# MainBoard.net
KiCad netlist of a schematic drawn in EAGLE
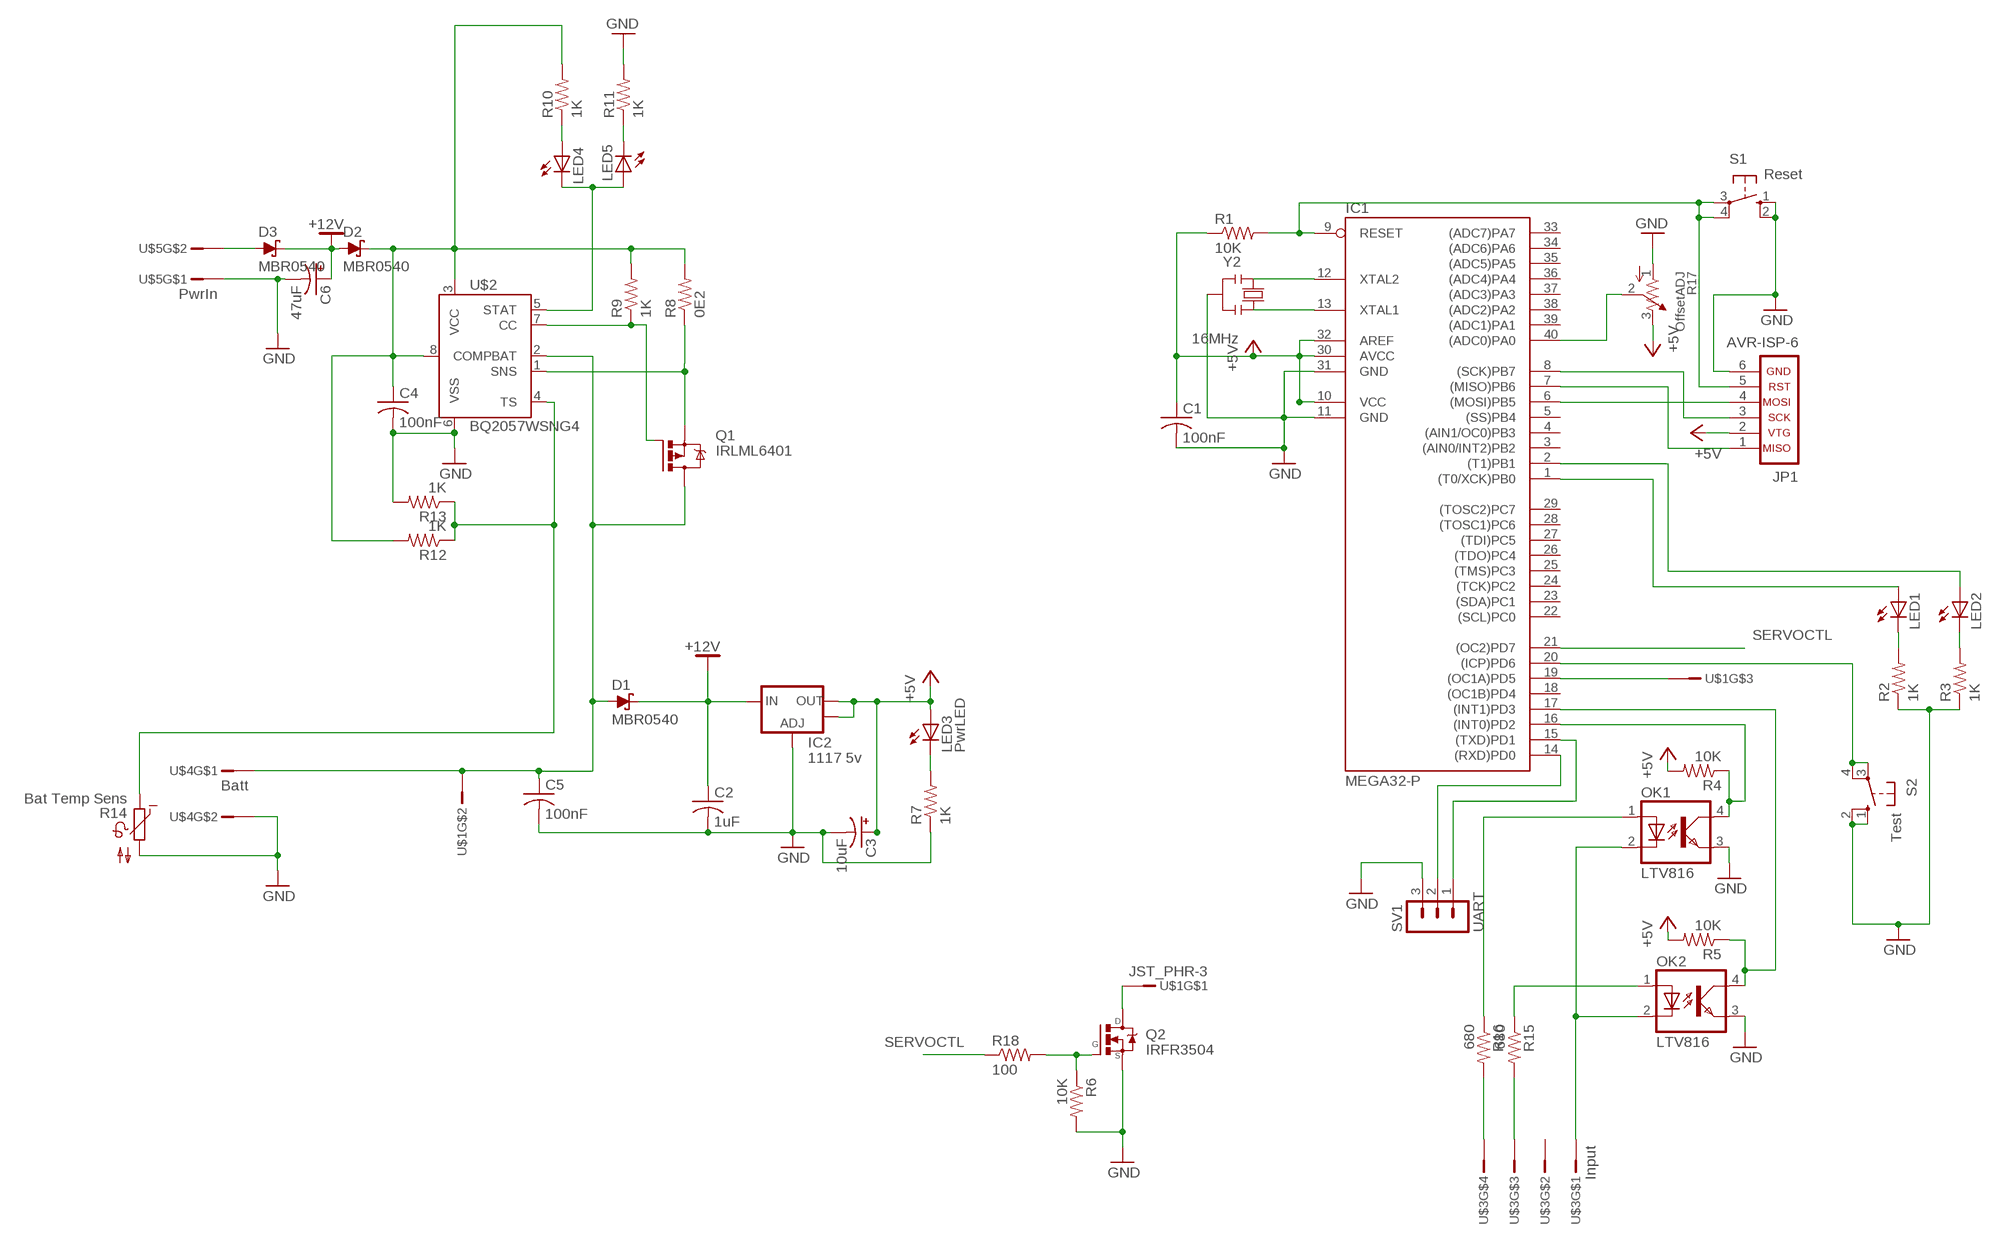
[diagram p0: schematic, sheet 1]

(export (version "E")
  (design (tool "Eeschema 10.0.6"))
  (components
    (comp (ref "C1")
      (value "100nF")
      (footprint "eagle-import:C0805K")
      (libsource (lib "eagle-import") (part "C-USC0805K"))
    )
    (comp (ref "C2")
      (value "1uF")
      (footprint "eagle-import:C0805K")
      (libsource (lib "eagle-import") (part "C-USC0805K"))
    )
    (comp (ref "C3")
      (value "10uF")
      (footprint "eagle-import:E2,5-7")
      (libsource (lib "eagle-import") (part "CPOL-USE2.5-7"))
    )
    (comp (ref "C4")
      (value "100nF")
      (footprint "eagle-import:C0805K")
      (libsource (lib "eagle-import") (part "C-USC0805K"))
    )
    (comp (ref "C5")
      (value "100nF")
      (footprint "eagle-import:C0805K")
      (libsource (lib "eagle-import") (part "C-USC0805K"))
    )
    (comp (ref "C6")
      (value "47uF")
      (footprint "eagle-import:E2,5-7")
      (libsource (lib "eagle-import") (part "CPOL-USE2.5-7"))
    )
    (comp (ref "D1")
      (value "MBR0540")
      (footprint "eagle-import:SOD123")
      (libsource (lib "eagle-import") (part "MBR0540"))
    )
    (comp (ref "D2")
      (value "MBR0540")
      (footprint "eagle-import:SOD123")
      (libsource (lib "eagle-import") (part "MBR0540"))
    )
    (comp (ref "D3")
      (value "MBR0540")
      (footprint "eagle-import:SOD123")
      (libsource (lib "eagle-import") (part "MBR0540"))
    )
    (comp (ref "IC1")
      (value "MEGA32-P")
      (footprint "eagle-import:DIL40")
      (fields (field (name "MPN") "ATMEGA32-16PU"))
      (libsource (lib "eagle-import") (part "MEGA32-P"))
    )
    (comp (ref "IC2")
      (value "1117 5v")
      (footprint "eagle-import:SOT223")
      (libsource (lib "eagle-import") (part "V_REG_LM1117SOT223"))
    )
    (comp (ref "JP1")
      (value "AVR-ISP-6")
      (footprint "eagle-import:AVR-ISP-6")
      (libsource (lib "eagle-import") (part "AVR-ISP-6"))
    )
    (comp (ref "LED1")
      (value "LED3MM")
      (footprint "eagle-import:LED3MM")
      (libsource (lib "eagle-import") (part "LED3MM"))
    )
    (comp (ref "LED2")
      (value "LED3MM")
      (footprint "eagle-import:LED3MM")
      (libsource (lib "eagle-import") (part "LED3MM"))
    )
    (comp (ref "LED3")
      (value "PwrLED")
      (footprint "eagle-import:LED3MM")
      (libsource (lib "eagle-import") (part "LED3MM"))
    )
    (comp (ref "LED4")
      (value "LED3MM")
      (footprint "eagle-import:LED3MM")
      (libsource (lib "eagle-import") (part "LED3MM"))
    )
    (comp (ref "LED5")
      (value "LED3MM")
      (footprint "eagle-import:LED3MM")
      (libsource (lib "eagle-import") (part "LED3MM"))
    )
    (comp (ref "OK1")
      (value "LTV816")
      (footprint "eagle-import:DIL04")
      (libsource (lib "eagle-import") (part "LTV816"))
    )
    (comp (ref "OK2")
      (value "LTV816")
      (footprint "eagle-import:DIL04")
      (libsource (lib "eagle-import") (part "LTV816"))
    )
    (comp (ref "Q1")
      (value "IRLML6401")
      (footprint "eagle-import:MICRO3")
      (libsource (lib "eagle-import") (part "IRLML5203"))
    )
    (comp (ref "Q2")
      (value "IRFR3504")
      (footprint "eagle-import:DPAK")
      (libsource (lib "eagle-import") (part "IRFR3504"))
    )
    (comp (ref "R1")
      (value "10K")
      (footprint "eagle-import:R0805")
      (libsource (lib "eagle-import") (part "R-US_R0805"))
    )
    (comp (ref "R2")
      (value "1K")
      (footprint "eagle-import:R0805")
      (libsource (lib "eagle-import") (part "R-US_R0805"))
    )
    (comp (ref "R3")
      (value "1K")
      (footprint "eagle-import:R0805")
      (libsource (lib "eagle-import") (part "R-US_R0805"))
    )
    (comp (ref "R4")
      (value "10K")
      (footprint "eagle-import:R0805")
      (libsource (lib "eagle-import") (part "R-US_R0805"))
    )
    (comp (ref "R5")
      (value "10K")
      (footprint "eagle-import:R0805")
      (libsource (lib "eagle-import") (part "R-US_R0805"))
    )
    (comp (ref "R6")
      (value "10K")
      (footprint "eagle-import:R0805")
      (libsource (lib "eagle-import") (part "R-US_R0805"))
    )
    (comp (ref "R7")
      (value "1K")
      (footprint "eagle-import:R0805")
      (libsource (lib "eagle-import") (part "R-US_R0805"))
    )
    (comp (ref "R8")
      (value "0E2")
      (footprint "eagle-import:M1206")
      (libsource (lib "eagle-import") (part "R-US_M1206"))
    )
    (comp (ref "R9")
      (value "1K")
      (footprint "eagle-import:R0805")
      (libsource (lib "eagle-import") (part "R-US_R0805"))
    )
    (comp (ref "R10")
      (value "1K")
      (footprint "eagle-import:R0805")
      (libsource (lib "eagle-import") (part "R-US_R0805"))
    )
    (comp (ref "R11")
      (value "1K")
      (footprint "eagle-import:R0805")
      (libsource (lib "eagle-import") (part "R-US_R0805"))
    )
    (comp (ref "R12")
      (value "1K")
      (footprint "eagle-import:R0805")
      (libsource (lib "eagle-import") (part "R-US_R0805"))
    )
    (comp (ref "R13")
      (value "1K")
      (footprint "eagle-import:R0805")
      (libsource (lib "eagle-import") (part "R-US_R0805"))
    )
    (comp (ref "R14")
      (value "Bat Temp Sens")
      (footprint "eagle-import:P640")
      (libsource (lib "eagle-import") (part "NTC640"))
    )
    (comp (ref "R15")
      (value "680")
      (footprint "eagle-import:R0805")
      (libsource (lib "eagle-import") (part "R-US_R0805"))
    )
    (comp (ref "R16")
      (value "680")
      (footprint "eagle-import:R0805")
      (libsource (lib "eagle-import") (part "R-US_R0805"))
    )
    (comp (ref "R17")
      (value "OffsetADJ")
      (footprint "eagle-import:3362P")
      (libsource (lib "eagle-import") (part "3362P"))
    )
    (comp (ref "R18")
      (value "100")
      (footprint "eagle-import:R0805")
      (libsource (lib "eagle-import") (part "R-US_R0805"))
    )
    (comp (ref "S1")
      (value "Reset")
      (footprint "eagle-import:B3F-10XX")
      (fields (field (name "MPN") "B3F-1000"))
      (libsource (lib "eagle-import") (part "10-XX"))
    )
    (comp (ref "S2")
      (value "Test")
      (footprint "eagle-import:B3F-10XX")
      (fields (field (name "MPN") "B3F-1000"))
      (libsource (lib "eagle-import") (part "10-XX"))
    )
    (comp (ref "SV1")
      (value "UART")
      (footprint "eagle-import:MA03-1")
      (libsource (lib "eagle-import") (part "MA03-1"))
    )
    (comp (ref "U$1")
      (value "JST_PHR-3")
      (footprint "eagle-import:PHR-3")
      (libsource (lib "eagle-import") (part "JST_PHR-3"))
    )
    (comp (ref "U$2")
      (value "BQ2057WSNG4")
      (footprint "eagle-import:D_R-PDSO-G8")
      (libsource (lib "eagle-import") (part "BQ2057WSNG4"))
    )
    (comp (ref "U$3")
      (value "Input")
      (footprint "eagle-import:PHR-4")
      (libsource (lib "eagle-import") (part "JST_PHR-4"))
    )
    (comp (ref "U$4")
      (value "Batt")
      (footprint "eagle-import:PHR-2")
      (libsource (lib "eagle-import") (part "JST_PHR-2"))
    )
    (comp (ref "U$5")
      (value "PwrIn")
      (footprint "eagle-import:PHR-2")
      (libsource (lib "eagle-import") (part "JST_PHR-2"))
    )
    (comp (ref "Y2")
      (value "16MHz")
      (footprint "eagle-import:RESONATOR")
      (libsource (lib "eagle-import") (part "RESONATORMU"))
    )
  )
  (nets
    (net (code "1") (name "+5V") (class "Default")
      (node (ref "C1") (pin "1") (pinfunction "1_1") (pintype "passive"))
      (node (ref "C3") (pin "+") (pinfunction "+_+") (pintype "passive"))
      (node (ref "IC1") (pin "10") (pinfunction "VCC_10") (pintype "power_in"))
      (node (ref "IC1") (pin "30") (pinfunction "AVCC_30") (pintype "power_in"))
      (node (ref "IC1") (pin "32") (pinfunction "AREF_32") (pintype "passive"))
      (node (ref "IC2") (pin "2") (pinfunction "OUT_2") (pintype "output"))
      (node (ref "IC2") (pin "4") (pinfunction "OUT_4") (pintype "output"))
      (node (ref "JP1") (pin "2") (pinfunction "2_2") (pintype "passive"))
      (node (ref "LED3") (pin "A") (pinfunction "A_A") (pintype "passive"))
      (node (ref "R1") (pin "1") (pinfunction "1_1") (pintype "passive"))
      (node (ref "R17") (pin "3") (pinfunction "3_3") (pintype "passive"))
      (node (ref "R4") (pin "2") (pinfunction "2_2") (pintype "passive"))
      (node (ref "R5") (pin "2") (pinfunction "2_2") (pintype "passive"))
    )
    (net (code "2") (name "+12V") (class "Default")
      (node (ref "C2") (pin "1") (pinfunction "1_1") (pintype "passive"))
      (node (ref "C6") (pin "+") (pinfunction "+_+") (pintype "passive"))
      (node (ref "D1") (pin "C") (pinfunction "C_C") (pintype "passive"))
      (node (ref "D2") (pin "A") (pinfunction "A_A") (pintype "passive"))
      (node (ref "D3") (pin "C") (pinfunction "C_C") (pintype "passive"))
      (node (ref "IC2") (pin "3") (pinfunction "IN_3") (pintype "input"))
    )
    (net (code "3") (name "/SERVOCTL") (class "Default")
      (node (ref "IC1") (pin "21") (pinfunction "(OC2)PD7_21") (pintype "bidirectional"))
      (node (ref "R18") (pin "1") (pinfunction "1_1") (pintype "passive"))
    )
    (net (code "4") (name "GND") (class "Default")
      (node (ref "C1") (pin "2") (pinfunction "2_2") (pintype "passive"))
      (node (ref "C2") (pin "2") (pinfunction "2_2") (pintype "passive"))
      (node (ref "C3") (pin "-") (pinfunction "-_-") (pintype "passive"))
      (node (ref "C4") (pin "2") (pinfunction "2_2") (pintype "passive"))
      (node (ref "C5") (pin "2") (pinfunction "2_2") (pintype "passive"))
      (node (ref "C6") (pin "-") (pinfunction "-_-") (pintype "passive"))
      (node (ref "IC1") (pin "11") (pinfunction "GND_11") (pintype "power_in"))
      (node (ref "IC1") (pin "31") (pinfunction "GND_31") (pintype "power_in"))
      (node (ref "IC2") (pin "1") (pinfunction "ADJ_1") (pintype "input"))
      (node (ref "JP1") (pin "6") (pinfunction "6_6") (pintype "passive"))
      (node (ref "OK1") (pin "3") (pinfunction "EMIT_3") (pintype "passive"))
      (node (ref "OK2") (pin "3") (pinfunction "EMIT_3") (pintype "passive"))
      (node (ref "Q2") (pin "3") (pinfunction "S_3") (pintype "passive"))
      (node (ref "R11") (pin "2") (pinfunction "2_2") (pintype "passive"))
      (node (ref "R13") (pin "2") (pinfunction "2_2") (pintype "passive"))
      (node (ref "R14") (pin "2") (pinfunction "2_2") (pintype "passive"))
      (node (ref "R17") (pin "1") (pinfunction "1_1") (pintype "passive"))
      (node (ref "R2") (pin "1") (pinfunction "1_1") (pintype "passive"))
      (node (ref "R3") (pin "1") (pinfunction "1_1") (pintype "passive"))
      (node (ref "R6") (pin "2") (pinfunction "2_2") (pintype "passive"))
      (node (ref "R7") (pin "1") (pinfunction "1_1") (pintype "passive"))
      (node (ref "S1") (pin "1") (pinfunction "S_1") (pintype "passive"))
      (node (ref "S1") (pin "2") (pinfunction "S1_2") (pintype "passive"))
      (node (ref "S2") (pin "1") (pinfunction "S_1") (pintype "passive"))
      (node (ref "S2") (pin "2") (pinfunction "S1_2") (pintype "passive"))
      (node (ref "SV1") (pin "3") (pinfunction "3_3") (pintype "passive"))
      (node (ref "U$2") (pin "6") (pinfunction "VSS_6") (pintype "power_in"))
      (node (ref "U$4") (pin "P$2") (pinfunction "1_P$2") (pintype "passive"))
      (node (ref "U$5") (pin "P$1") (pinfunction "1_P$1") (pintype "passive"))
      (node (ref "Y2") (pin "2") (pinfunction "2_2") (pintype "passive"))
    )
    (net (code "5") (name "Net-(IC1-(ADC0)PA0)") (class "Default")
      (node (ref "IC1") (pin "40") (pinfunction "(ADC0)PA0_40") (pintype "bidirectional"))
      (node (ref "R17") (pin "2") (pinfunction "2_2") (pintype "passive"))
    )
    (net (code "6") (name "Net-(IC1-(ICP)PD6)") (class "Default")
      (node (ref "IC1") (pin "20") (pinfunction "(ICP)PD6_20") (pintype "bidirectional"))
      (node (ref "S2") (pin "3") (pinfunction "P_3") (pintype "passive"))
      (node (ref "S2") (pin "4") (pinfunction "P1_4") (pintype "passive"))
    )
    (net (code "7") (name "Net-(IC1-(INT0)PD2)") (class "Default")
      (node (ref "IC1") (pin "16") (pinfunction "(INT0)PD2_16") (pintype "bidirectional"))
      (node (ref "OK1") (pin "4") (pinfunction "COL_4") (pintype "passive"))
      (node (ref "R4") (pin "1") (pinfunction "1_1") (pintype "passive"))
    )
    (net (code "8") (name "Net-(IC1-(INT1)PD3)") (class "Default")
      (node (ref "IC1") (pin "17") (pinfunction "(INT1)PD3_17") (pintype "bidirectional"))
      (node (ref "OK2") (pin "4") (pinfunction "COL_4") (pintype "passive"))
      (node (ref "R5") (pin "1") (pinfunction "1_1") (pintype "passive"))
    )
    (net (code "9") (name "Net-(IC1-(MISO)PB6)") (class "Default")
      (node (ref "IC1") (pin "7") (pinfunction "(MISO)PB6_7") (pintype "bidirectional"))
      (node (ref "JP1") (pin "1") (pinfunction "1_1") (pintype "passive"))
    )
    (net (code "10") (name "Net-(IC1-(MOSI)PB5)") (class "Default")
      (node (ref "IC1") (pin "6") (pinfunction "(MOSI)PB5_6") (pintype "bidirectional"))
      (node (ref "JP1") (pin "4") (pinfunction "4_4") (pintype "passive"))
    )
    (net (code "11") (name "Net-(IC1-(OC1A)PD5)") (class "Default")
      (node (ref "IC1") (pin "19") (pinfunction "(OC1A)PD5_19") (pintype "bidirectional"))
      (node (ref "U$1") (pin "P$3") (pinfunction "1_P$3") (pintype "passive"))
    )
    (net (code "12") (name "Net-(IC1-(RXD)PD0)") (class "Default")
      (node (ref "IC1") (pin "14") (pinfunction "(RXD)PD0_14") (pintype "bidirectional"))
      (node (ref "SV1") (pin "2") (pinfunction "2_2") (pintype "passive"))
    )
    (net (code "13") (name "Net-(IC1-(SCK)PB7)") (class "Default")
      (node (ref "IC1") (pin "8") (pinfunction "(SCK)PB7_8") (pintype "bidirectional"))
      (node (ref "JP1") (pin "3") (pinfunction "3_3") (pintype "passive"))
    )
    (net (code "14") (name "Net-(IC1-(T0{slash}XCK)PB0)") (class "Default")
      (node (ref "IC1") (pin "1") (pinfunction "(T0/XCK)PB0_1") (pintype "bidirectional"))
      (node (ref "LED1") (pin "A") (pinfunction "A_A") (pintype "passive"))
    )
    (net (code "15") (name "Net-(IC1-(T1)PB1)") (class "Default")
      (node (ref "IC1") (pin "2") (pinfunction "(T1)PB1_2") (pintype "bidirectional"))
      (node (ref "LED2") (pin "A") (pinfunction "A_A") (pintype "passive"))
    )
    (net (code "16") (name "Net-(IC1-(TXD)PD1)") (class "Default")
      (node (ref "IC1") (pin "15") (pinfunction "(TXD)PD1_15") (pintype "bidirectional"))
      (node (ref "SV1") (pin "1") (pinfunction "1_1") (pintype "passive"))
    )
    (net (code "17") (name "Net-(IC1-RESET)") (class "Default")
      (node (ref "IC1") (pin "9") (pinfunction "RESET_9") (pintype "input"))
      (node (ref "JP1") (pin "5") (pinfunction "5_5") (pintype "passive"))
      (node (ref "R1") (pin "2") (pinfunction "2_2") (pintype "passive"))
      (node (ref "S1") (pin "3") (pinfunction "P_3") (pintype "passive"))
      (node (ref "S1") (pin "4") (pinfunction "P1_4") (pintype "passive"))
    )
    (net (code "18") (name "Net-(IC1-XTAL1)") (class "Default")
      (node (ref "IC1") (pin "13") (pinfunction "XTAL1_13") (pintype "bidirectional"))
      (node (ref "Y2") (pin "3") (pinfunction "3_3") (pintype "passive"))
    )
    (net (code "19") (name "Net-(IC1-XTAL2)") (class "Default")
      (node (ref "IC1") (pin "12") (pinfunction "XTAL2_12") (pintype "bidirectional"))
      (node (ref "Y2") (pin "1") (pinfunction "1_1") (pintype "passive"))
    )
    (net (code "20") (name "Net-(LED1-C)") (class "Default")
      (node (ref "LED1") (pin "K") (pinfunction "C_K") (pintype "passive"))
      (node (ref "R2") (pin "2") (pinfunction "2_2") (pintype "passive"))
    )
    (net (code "21") (name "Net-(LED2-C)") (class "Default")
      (node (ref "LED2") (pin "K") (pinfunction "C_K") (pintype "passive"))
      (node (ref "R3") (pin "2") (pinfunction "2_2") (pintype "passive"))
    )
    (net (code "22") (name "Net-(LED3-C)") (class "Default")
      (node (ref "LED3") (pin "K") (pinfunction "C_K") (pintype "passive"))
      (node (ref "R7") (pin "2") (pinfunction "2_2") (pintype "passive"))
    )
    (net (code "23") (name "Net-(LED4-C)") (class "Default")
      (node (ref "LED4") (pin "K") (pinfunction "C_K") (pintype "passive"))
      (node (ref "LED5") (pin "A") (pinfunction "A_A") (pintype "passive"))
      (node (ref "U$2") (pin "5") (pinfunction "STAT_5") (pintype "output"))
    )
    (net (code "24") (name "Net-(LED4-PadA)") (class "Default")
      (node (ref "LED4") (pin "A") (pinfunction "A_A") (pintype "passive"))
      (node (ref "R10") (pin "1") (pinfunction "1_1") (pintype "passive"))
    )
    (net (code "25") (name "Net-(LED5-C)") (class "Default")
      (node (ref "LED5") (pin "K") (pinfunction "C_K") (pintype "passive"))
      (node (ref "R11") (pin "1") (pinfunction "1_1") (pintype "passive"))
    )
    (net (code "26") (name "Net-(OK1-A)") (class "Default")
      (node (ref "OK1") (pin "1") (pinfunction "A_1") (pintype "passive"))
      (node (ref "R16") (pin "1") (pinfunction "1_1") (pintype "passive"))
    )
    (net (code "27") (name "Net-(OK1-C)") (class "Default")
      (node (ref "OK1") (pin "2") (pinfunction "C_2") (pintype "passive"))
      (node (ref "OK2") (pin "2") (pinfunction "C_2") (pintype "passive"))
      (node (ref "U$3") (pin "P$1") (pinfunction "1_P$1") (pintype "passive"))
    )
    (net (code "28") (name "Net-(OK2-A)") (class "Default")
      (node (ref "OK2") (pin "1") (pinfunction "A_1") (pintype "passive"))
      (node (ref "R15") (pin "1") (pinfunction "1_1") (pintype "passive"))
    )
    (net (code "29") (name "Net-(Q1-D)") (class "Default")
      (node (ref "C5") (pin "1") (pinfunction "1_1") (pintype "passive"))
      (node (ref "D1") (pin "A") (pinfunction "A_A") (pintype "passive"))
      (node (ref "Q1") (pin "3") (pinfunction "D_3") (pintype "passive"))
      (node (ref "U$1") (pin "P$2") (pinfunction "1_P$2") (pintype "passive"))
      (node (ref "U$2") (pin "2") (pinfunction "BAT_2") (pintype "input"))
      (node (ref "U$4") (pin "P$1") (pinfunction "1_P$1") (pintype "passive"))
    )
    (net (code "30") (name "Net-(Q1-G)") (class "Default")
      (node (ref "Q1") (pin "1") (pinfunction "G_1") (pintype "passive"))
      (node (ref "R9") (pin "1") (pinfunction "1_1") (pintype "passive"))
      (node (ref "U$2") (pin "7") (pinfunction "CC_7") (pintype "output"))
    )
    (net (code "31") (name "Net-(Q1-S)") (class "Default")
      (node (ref "Q1") (pin "2") (pinfunction "S_2") (pintype "passive"))
      (node (ref "R8") (pin "1") (pinfunction "1_1") (pintype "passive"))
      (node (ref "U$2") (pin "1") (pinfunction "SNS_1") (pintype "input"))
    )
    (net (code "32") (name "Net-(Q2-D)") (class "Default")
      (node (ref "Q2") (pin "4") (pinfunction "D_4") (pintype "passive"))
      (node (ref "U$1") (pin "P$1") (pinfunction "1_P$1") (pintype "passive"))
    )
    (net (code "33") (name "Net-(Q2-G)") (class "Default")
      (node (ref "Q2") (pin "1") (pinfunction "G_1") (pintype "passive"))
      (node (ref "R18") (pin "2") (pinfunction "2_2") (pintype "passive"))
      (node (ref "R6") (pin "1") (pinfunction "1_1") (pintype "passive"))
    )
    (net (code "34") (name "Net-(U$2-COMP)") (class "Default")
      (node (ref "C4") (pin "1") (pinfunction "1_1") (pintype "passive"))
      (node (ref "D2") (pin "C") (pinfunction "C_C") (pintype "passive"))
      (node (ref "R10") (pin "2") (pinfunction "2_2") (pintype "passive"))
      (node (ref "R12") (pin "2") (pinfunction "2_2") (pintype "passive"))
      (node (ref "R8") (pin "2") (pinfunction "2_2") (pintype "passive"))
      (node (ref "R9") (pin "2") (pinfunction "2_2") (pintype "passive"))
      (node (ref "U$2") (pin "3") (pinfunction "VCC_3") (pintype "input"))
      (node (ref "U$2") (pin "8") (pinfunction "COMP_8") (pintype "input"))
    )
    (net (code "35") (name "Net-(U$2-TS)") (class "Default")
      (node (ref "R12") (pin "1") (pinfunction "1_1") (pintype "passive"))
      (node (ref "R13") (pin "1") (pinfunction "1_1") (pintype "passive"))
      (node (ref "R14") (pin "1") (pinfunction "1_1") (pintype "passive"))
      (node (ref "U$2") (pin "4") (pinfunction "TS_4") (pintype "input"))
    )
    (net (code "36") (name "Net-(U$3C-1)") (class "Default")
      (node (ref "R15") (pin "2") (pinfunction "2_2") (pintype "passive"))
      (node (ref "U$3") (pin "P$3") (pinfunction "1_P$3") (pintype "passive"))
    )
    (net (code "37") (name "Net-(U$3D-1)") (class "Default")
      (node (ref "R16") (pin "2") (pinfunction "2_2") (pintype "passive"))
      (node (ref "U$3") (pin "P$4") (pinfunction "1_P$4") (pintype "passive"))
    )
    (net (code "38") (name "Net-(U$5B-1)") (class "Default")
      (node (ref "D3") (pin "A") (pinfunction "A_A") (pintype "passive"))
      (node (ref "U$5") (pin "P$2") (pinfunction "1_P$2") (pintype "passive"))
    )
    (net (code "39") (name "unconnected-(IC1-(ADC1)PA1-Pad39)") (class "Default")
      (node (ref "IC1") (pin "39") (pinfunction "(ADC1)PA1_39") (pintype "bidirectional"))
    )
    (net (code "40") (name "unconnected-(IC1-(ADC2)PA2-Pad38)") (class "Default")
      (node (ref "IC1") (pin "38") (pinfunction "(ADC2)PA2_38") (pintype "bidirectional"))
    )
    (net (code "41") (name "unconnected-(IC1-(ADC3)PA3-Pad37)") (class "Default")
      (node (ref "IC1") (pin "37") (pinfunction "(ADC3)PA3_37") (pintype "bidirectional"))
    )
    (net (code "42") (name "unconnected-(IC1-(ADC4)PA4-Pad36)") (class "Default")
      (node (ref "IC1") (pin "36") (pinfunction "(ADC4)PA4_36") (pintype "bidirectional"))
    )
    (net (code "43") (name "unconnected-(IC1-(ADC5)PA5-Pad35)") (class "Default")
      (node (ref "IC1") (pin "35") (pinfunction "(ADC5)PA5_35") (pintype "bidirectional"))
    )
    (net (code "44") (name "unconnected-(IC1-(ADC6)PA6-Pad34)") (class "Default")
      (node (ref "IC1") (pin "34") (pinfunction "(ADC6)PA6_34") (pintype "bidirectional"))
    )
    (net (code "45") (name "unconnected-(IC1-(ADC7)PA7-Pad33)") (class "Default")
      (node (ref "IC1") (pin "33") (pinfunction "(ADC7)PA7_33") (pintype "bidirectional"))
    )
    (net (code "46") (name "unconnected-(IC1-(AIN0{slash}INT2)PB2-Pad3)") (class "Default")
      (node (ref "IC1") (pin "3") (pinfunction "(AIN0/INT2)PB2_3") (pintype "bidirectional"))
    )
    (net (code "47") (name "unconnected-(IC1-(AIN1{slash}OC0)PB3-Pad4)") (class "Default")
      (node (ref "IC1") (pin "4") (pinfunction "(AIN1/OC0)PB3_4") (pintype "bidirectional"))
    )
    (net (code "48") (name "unconnected-(IC1-(OC1B)PD4-Pad18)") (class "Default")
      (node (ref "IC1") (pin "18") (pinfunction "(OC1B)PD4_18") (pintype "bidirectional"))
    )
    (net (code "49") (name "unconnected-(IC1-(SCL)PC0-Pad22)") (class "Default")
      (node (ref "IC1") (pin "22") (pinfunction "(SCL)PC0_22") (pintype "bidirectional"))
    )
    (net (code "50") (name "unconnected-(IC1-(SDA)PC1-Pad23)") (class "Default")
      (node (ref "IC1") (pin "23") (pinfunction "(SDA)PC1_23") (pintype "bidirectional"))
    )
    (net (code "51") (name "unconnected-(IC1-(SS)PB4-Pad5)") (class "Default")
      (node (ref "IC1") (pin "5") (pinfunction "(SS)PB4_5") (pintype "bidirectional"))
    )
    (net (code "52") (name "unconnected-(IC1-(TCK)PC2-Pad24)") (class "Default")
      (node (ref "IC1") (pin "24") (pinfunction "(TCK)PC2_24") (pintype "bidirectional"))
    )
    (net (code "53") (name "unconnected-(IC1-(TDI)PC5-Pad27)") (class "Default")
      (node (ref "IC1") (pin "27") (pinfunction "(TDI)PC5_27") (pintype "bidirectional"))
    )
    (net (code "54") (name "unconnected-(IC1-(TDO)PC4-Pad26)") (class "Default")
      (node (ref "IC1") (pin "26") (pinfunction "(TDO)PC4_26") (pintype "bidirectional"))
    )
    (net (code "55") (name "unconnected-(IC1-(TMS)PC3-Pad25)") (class "Default")
      (node (ref "IC1") (pin "25") (pinfunction "(TMS)PC3_25") (pintype "bidirectional"))
    )
    (net (code "56") (name "unconnected-(IC1-(TOSC1)PC6-Pad28)") (class "Default")
      (node (ref "IC1") (pin "28") (pinfunction "(TOSC1)PC6_28") (pintype "bidirectional"))
    )
    (net (code "57") (name "unconnected-(IC1-(TOSC2)PC7-Pad29)") (class "Default")
      (node (ref "IC1") (pin "29") (pinfunction "(TOSC2)PC7_29") (pintype "bidirectional"))
    )
    (net (code "58") (name "unconnected-(U$3B-1-PadP$2)") (class "Default")
      (node (ref "U$3") (pin "P$2") (pinfunction "1_P$2") (pintype "passive"))
    )
  )
)
